# Sensors.net
KiCad netlist of a schematic drawn in EAGLE
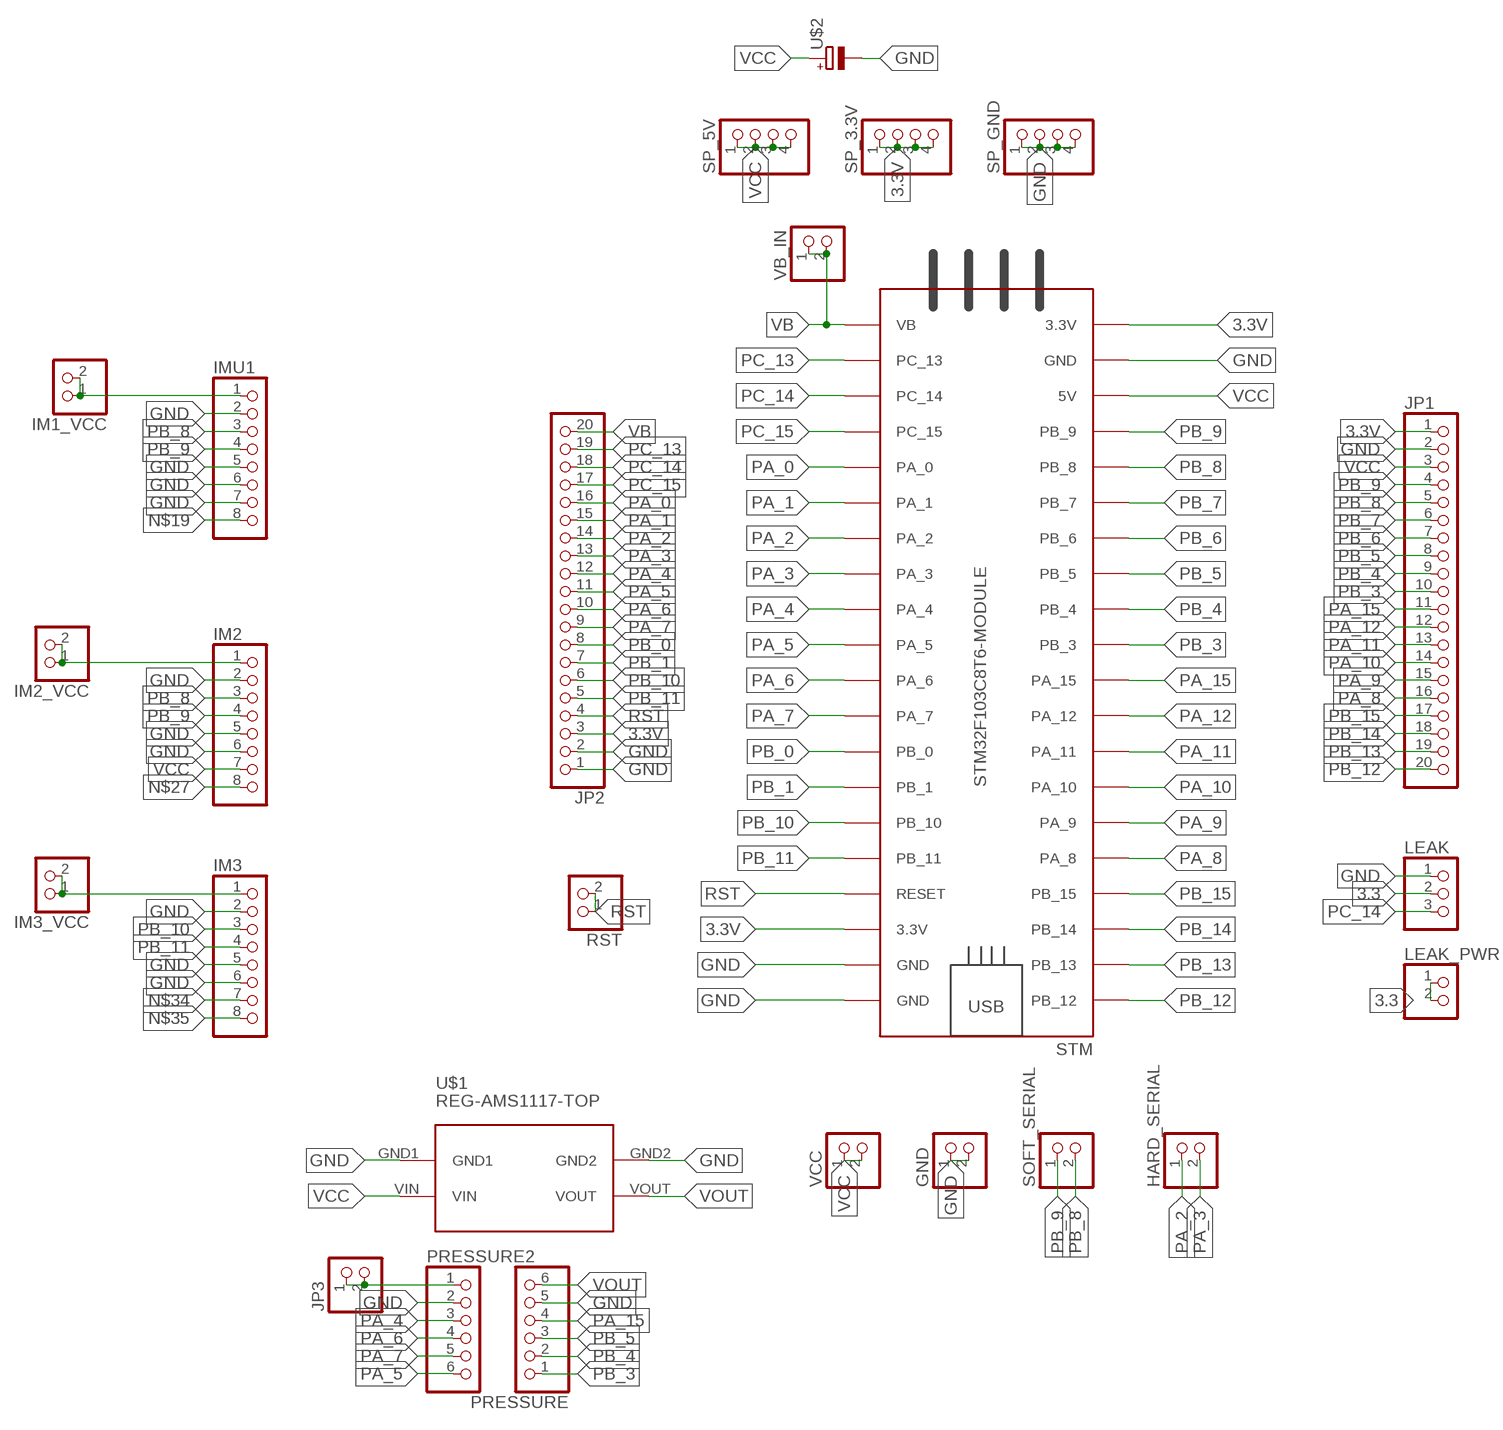
[diagram p0: schematic, sheet 1]

(export (version "E")
  (design (tool "Eeschema 10.0.6"))
  (components
    (comp (ref "GND")
      (value "PINHD-2_DATA")
      (footprint "eagle-import:1X02_DATA")
      (libsource (lib "eagle-import") (part "PINHD-2_DATA"))
    )
    (comp (ref "HARD_SERIAL")
      (value "PINHD-2_DATA")
      (footprint "eagle-import:1X02_DATA")
      (libsource (lib "eagle-import") (part "PINHD-2_DATA"))
    )
    (comp (ref "IM1_VCC")
      (value "PINHD-2_DATA")
      (footprint "eagle-import:1X02_DATA")
      (libsource (lib "eagle-import") (part "PINHD-2_DATA"))
    )
    (comp (ref "IM2")
      (value "PINHD-8_DATA")
      (footprint "eagle-import:1X08_DATA")
      (libsource (lib "eagle-import") (part "PINHD-8_DATA"))
    )
    (comp (ref "IM2_VCC")
      (value "PINHD-2_DATA")
      (footprint "eagle-import:1X02_DATA")
      (libsource (lib "eagle-import") (part "PINHD-2_DATA"))
    )
    (comp (ref "IM3")
      (value "PINHD-8_DATA")
      (footprint "eagle-import:1X08_DATA")
      (libsource (lib "eagle-import") (part "PINHD-8_DATA"))
    )
    (comp (ref "IM3_VCC")
      (value "PINHD-2_DATA")
      (footprint "eagle-import:1X02_DATA")
      (libsource (lib "eagle-import") (part "PINHD-2_DATA"))
    )
    (comp (ref "IMU1")
      (value "PINHD-8_DATA")
      (footprint "eagle-import:1X08_DATA")
      (libsource (lib "eagle-import") (part "PINHD-8_DATA"))
    )
    (comp (ref "JP1")
      (value "PINHD-1X20")
      (footprint "eagle-import:1X20")
      (libsource (lib "eagle-import") (part "PINHD-1X20"))
    )
    (comp (ref "JP2")
      (value "PINHD-1X20")
      (footprint "eagle-import:1X20")
      (libsource (lib "eagle-import") (part "PINHD-1X20"))
    )
    (comp (ref "JP3")
      (value "PINHD-2_DATA")
      (footprint "eagle-import:1X02_DATA")
      (libsource (lib "eagle-import") (part "PINHD-2_DATA"))
    )
    (comp (ref "LEAK")
      (value "PINHD-3_DATA")
      (footprint "eagle-import:1X03_DATA")
      (libsource (lib "eagle-import") (part "PINHD-3_DATA"))
    )
    (comp (ref "LEAK_PWR")
      (value "PINHD-2_DATA")
      (footprint "eagle-import:1X02_DATA")
      (libsource (lib "eagle-import") (part "PINHD-2_DATA"))
    )
    (comp (ref "PRESSURE")
      (value "PINHD-6_DATA")
      (footprint "eagle-import:1X06_DATA")
      (libsource (lib "eagle-import") (part "PINHD-6_DATA"))
    )
    (comp (ref "PRESSURE2")
      (value "PINHD-6_DATA")
      (footprint "eagle-import:1X06_DATA")
      (libsource (lib "eagle-import") (part "PINHD-6_DATA"))
    )
    (comp (ref "RST")
      (value "PINHD-2_DATA")
      (footprint "eagle-import:1X02_DATA")
      (libsource (lib "eagle-import") (part "PINHD-2_DATA"))
    )
    (comp (ref "SOFT_SERIAL")
      (value "PINHD-2_DATA")
      (footprint "eagle-import:1X02_DATA")
      (libsource (lib "eagle-import") (part "PINHD-2_DATA"))
    )
    (comp (ref "SP_3.3V")
      (value "PINHD-1X4")
      (footprint "eagle-import:1X04")
      (libsource (lib "eagle-import") (part "PINHD-1X4"))
    )
    (comp (ref "SP_5V")
      (value "PINHD-1X4")
      (footprint "eagle-import:1X04")
      (libsource (lib "eagle-import") (part "PINHD-1X4"))
    )
    (comp (ref "SP_GND")
      (value "PINHD-1X4")
      (footprint "eagle-import:1X04")
      (libsource (lib "eagle-import") (part "PINHD-1X4"))
    )
    (comp (ref "STM")
      (value "STM32F103C8T6-MODULE")
      (footprint "eagle-import:STM32F103C8T6-MODULE")
      (libsource (lib "eagle-import") (part "STM32F103C8T6-MODULE"))
    )
    (comp (ref "U$1")
      (value "REG-AMS1117-TOP")
      (footprint "eagle-import:REG-AMS1117_TOP")
      (libsource (lib "eagle-import") (part "REG-AMS1117-TOP"))
    )
    (comp (ref "U$2")
      (value "CAP_POL")
      (footprint "eagle-import:E3,5-8")
      (libsource (lib "eagle-import") (part "CAP_POL"))
    )
    (comp (ref "VB_IN")
      (value "PINHD-2_DATA")
      (footprint "eagle-import:1X02_DATA")
      (libsource (lib "eagle-import") (part "PINHD-2_DATA"))
    )
    (comp (ref "VCC")
      (value "PINHD-2_DATA")
      (footprint "eagle-import:1X02_DATA")
      (libsource (lib "eagle-import") (part "PINHD-2_DATA"))
    )
  )
  (nets
    (net (code "1") (name "3.3") (class "Default")
      (node (ref "LEAK") (pin "2") (pinfunction "2_2") (pintype "passive"))
      (node (ref "LEAK_PWR") (pin "1") (pinfunction "1_1") (pintype "passive"))
      (node (ref "LEAK_PWR") (pin "2") (pinfunction "2_2") (pintype "passive"))
    )
    (net (code "2") (name "3.3V") (class "Default")
      (node (ref "JP1") (pin "1") (pinfunction "1_1") (pintype "passive"))
      (node (ref "JP2") (pin "3") (pinfunction "3_3") (pintype "passive"))
      (node (ref "SP_3.3V") (pin "1") (pinfunction "1_1") (pintype "passive"))
      (node (ref "SP_3.3V") (pin "2") (pinfunction "2_2") (pintype "passive"))
      (node (ref "SP_3.3V") (pin "3") (pinfunction "3_3") (pintype "passive"))
      (node (ref "SP_3.3V") (pin "4") (pinfunction "4_4") (pintype "passive"))
      (node (ref "STM") (pin "3.3V_1") (pinfunction "3.3V_3.3V_1") (pintype "bidirectional"))
      (node (ref "STM") (pin "3.3V_2") (pinfunction "3.3V_3.3V_2") (pintype "bidirectional"))
    )
    (net (code "3") (name "GND") (class "Default")
      (node (ref "GND") (pin "1") (pinfunction "1_1") (pintype "passive"))
      (node (ref "GND") (pin "2") (pinfunction "2_2") (pintype "passive"))
      (node (ref "IM2") (pin "2") (pinfunction "2_2") (pintype "passive"))
      (node (ref "IM2") (pin "5") (pinfunction "5_5") (pintype "passive"))
      (node (ref "IM2") (pin "6") (pinfunction "6_6") (pintype "passive"))
      (node (ref "IM3") (pin "2") (pinfunction "2_2") (pintype "passive"))
      (node (ref "IM3") (pin "5") (pinfunction "5_5") (pintype "passive"))
      (node (ref "IM3") (pin "6") (pinfunction "6_6") (pintype "passive"))
      (node (ref "IMU1") (pin "2") (pinfunction "2_2") (pintype "passive"))
      (node (ref "IMU1") (pin "5") (pinfunction "5_5") (pintype "passive"))
      (node (ref "IMU1") (pin "6") (pinfunction "6_6") (pintype "passive"))
      (node (ref "IMU1") (pin "7") (pinfunction "7_7") (pintype "passive"))
      (node (ref "JP1") (pin "2") (pinfunction "2_2") (pintype "passive"))
      (node (ref "JP2") (pin "1") (pinfunction "1_1") (pintype "passive"))
      (node (ref "JP2") (pin "2") (pinfunction "2_2") (pintype "passive"))
      (node (ref "LEAK") (pin "1") (pinfunction "1_1") (pintype "passive"))
      (node (ref "PRESSURE") (pin "5") (pinfunction "5_5") (pintype "passive"))
      (node (ref "PRESSURE2") (pin "2") (pinfunction "2_2") (pintype "passive"))
      (node (ref "SP_GND") (pin "1") (pinfunction "1_1") (pintype "passive"))
      (node (ref "SP_GND") (pin "2") (pinfunction "2_2") (pintype "passive"))
      (node (ref "SP_GND") (pin "3") (pinfunction "3_3") (pintype "passive"))
      (node (ref "SP_GND") (pin "4") (pinfunction "4_4") (pintype "passive"))
      (node (ref "STM") (pin "GND_1") (pinfunction "GND_GND_1") (pintype "bidirectional"))
      (node (ref "STM") (pin "GND_2") (pinfunction "GND_GND_2") (pintype "bidirectional"))
      (node (ref "STM") (pin "GND_3") (pinfunction "GND_GND_3") (pintype "power_in"))
      (node (ref "U$1") (pin "GND1") (pinfunction "GND1_GND1") (pintype "bidirectional"))
      (node (ref "U$1") (pin "GND2") (pinfunction "GND2_GND2") (pintype "bidirectional"))
      (node (ref "U$2") (pin "-") (pinfunction "-_-") (pintype "passive"))
    )
    (net (code "4") (name "N$19") (class "Default")
      (node (ref "IMU1") (pin "8") (pinfunction "8_8") (pintype "passive"))
    )
    (net (code "5") (name "N$27") (class "Default")
      (node (ref "IM2") (pin "8") (pinfunction "8_8") (pintype "passive"))
    )
    (net (code "6") (name "N$34") (class "Default")
      (node (ref "IM3") (pin "7") (pinfunction "7_7") (pintype "passive"))
    )
    (net (code "7") (name "N$35") (class "Default")
      (node (ref "IM3") (pin "8") (pinfunction "8_8") (pintype "passive"))
    )
    (net (code "8") (name "Net-(IM1_VCC-Pad1)") (class "Default")
      (node (ref "IM1_VCC") (pin "1") (pinfunction "1_1") (pintype "passive"))
      (node (ref "IM1_VCC") (pin "2") (pinfunction "2_2") (pintype "passive"))
      (node (ref "IMU1") (pin "1") (pinfunction "1_1") (pintype "passive"))
    )
    (net (code "9") (name "Net-(IM2-Pad1)") (class "Default")
      (node (ref "IM2") (pin "1") (pinfunction "1_1") (pintype "passive"))
      (node (ref "IM2_VCC") (pin "1") (pinfunction "1_1") (pintype "passive"))
      (node (ref "IM2_VCC") (pin "2") (pinfunction "2_2") (pintype "passive"))
    )
    (net (code "10") (name "Net-(IM3-Pad1)") (class "Default")
      (node (ref "IM3") (pin "1") (pinfunction "1_1") (pintype "passive"))
      (node (ref "IM3_VCC") (pin "1") (pinfunction "1_1") (pintype "passive"))
      (node (ref "IM3_VCC") (pin "2") (pinfunction "2_2") (pintype "passive"))
    )
    (net (code "11") (name "Net-(JP3-Pad1)") (class "Default")
      (node (ref "JP3") (pin "1") (pinfunction "1_1") (pintype "passive"))
      (node (ref "JP3") (pin "2") (pinfunction "2_2") (pintype "passive"))
      (node (ref "PRESSURE2") (pin "1") (pinfunction "1_1") (pintype "passive"))
    )
    (net (code "12") (name "PA_0") (class "Default")
      (node (ref "JP2") (pin "16") (pinfunction "16_16") (pintype "passive"))
      (node (ref "STM") (pin "PA_0") (pinfunction "PA_0_PA_0") (pintype "bidirectional"))
    )
    (net (code "13") (name "PA_1") (class "Default")
      (node (ref "JP2") (pin "15") (pinfunction "15_15") (pintype "passive"))
      (node (ref "STM") (pin "PA_1") (pinfunction "PA_1_PA_1") (pintype "bidirectional"))
    )
    (net (code "14") (name "PA_2") (class "Default")
      (node (ref "HARD_SERIAL") (pin "1") (pinfunction "1_1") (pintype "passive"))
      (node (ref "JP2") (pin "14") (pinfunction "14_14") (pintype "passive"))
      (node (ref "STM") (pin "PA_2") (pinfunction "PA_2_PA_2") (pintype "bidirectional"))
    )
    (net (code "15") (name "PA_3") (class "Default")
      (node (ref "HARD_SERIAL") (pin "2") (pinfunction "2_2") (pintype "passive"))
      (node (ref "JP2") (pin "13") (pinfunction "13_13") (pintype "passive"))
      (node (ref "STM") (pin "PA_3") (pinfunction "PA_3_PA_3") (pintype "bidirectional"))
    )
    (net (code "16") (name "PA_4") (class "Default")
      (node (ref "JP2") (pin "12") (pinfunction "12_12") (pintype "passive"))
      (node (ref "PRESSURE2") (pin "3") (pinfunction "3_3") (pintype "passive"))
      (node (ref "STM") (pin "PA_4") (pinfunction "PA_4_PA_4") (pintype "bidirectional"))
    )
    (net (code "17") (name "PA_5") (class "Default")
      (node (ref "JP2") (pin "11") (pinfunction "11_11") (pintype "passive"))
      (node (ref "PRESSURE2") (pin "6") (pinfunction "6_6") (pintype "passive"))
      (node (ref "STM") (pin "PA_5") (pinfunction "PA_5_PA_5") (pintype "bidirectional"))
    )
    (net (code "18") (name "PA_6") (class "Default")
      (node (ref "JP2") (pin "10") (pinfunction "10_10") (pintype "passive"))
      (node (ref "PRESSURE2") (pin "4") (pinfunction "4_4") (pintype "passive"))
      (node (ref "STM") (pin "PA_6") (pinfunction "PA_6_PA_6") (pintype "bidirectional"))
    )
    (net (code "19") (name "PA_7") (class "Default")
      (node (ref "JP2") (pin "9") (pinfunction "9_9") (pintype "passive"))
      (node (ref "PRESSURE2") (pin "5") (pinfunction "5_5") (pintype "passive"))
      (node (ref "STM") (pin "PA_7") (pinfunction "PA_7_PA_7") (pintype "bidirectional"))
    )
    (net (code "20") (name "PA_8") (class "Default")
      (node (ref "JP1") (pin "16") (pinfunction "16_16") (pintype "passive"))
      (node (ref "STM") (pin "PA_8") (pinfunction "PA_8_PA_8") (pintype "bidirectional"))
    )
    (net (code "21") (name "PA_9") (class "Default")
      (node (ref "JP1") (pin "15") (pinfunction "15_15") (pintype "passive"))
      (node (ref "STM") (pin "PA_9") (pinfunction "PA_9_PA_9") (pintype "bidirectional"))
    )
    (net (code "22") (name "PA_10") (class "Default")
      (node (ref "JP1") (pin "14") (pinfunction "14_14") (pintype "passive"))
      (node (ref "STM") (pin "PA_10") (pinfunction "PA_10_PA_10") (pintype "bidirectional"))
    )
    (net (code "23") (name "PA_11") (class "Default")
      (node (ref "JP1") (pin "13") (pinfunction "13_13") (pintype "passive"))
      (node (ref "STM") (pin "PA_11") (pinfunction "PA_11_PA_11") (pintype "bidirectional"))
    )
    (net (code "24") (name "PA_12") (class "Default")
      (node (ref "JP1") (pin "12") (pinfunction "12_12") (pintype "passive"))
      (node (ref "STM") (pin "PA_12") (pinfunction "PA_12_PA_12") (pintype "bidirectional"))
    )
    (net (code "25") (name "PA_15") (class "Default")
      (node (ref "JP1") (pin "11") (pinfunction "11_11") (pintype "passive"))
      (node (ref "PRESSURE") (pin "4") (pinfunction "4_4") (pintype "passive"))
      (node (ref "STM") (pin "PA_15") (pinfunction "PA_15_PA_15") (pintype "bidirectional"))
    )
    (net (code "26") (name "PB_0") (class "Default")
      (node (ref "JP2") (pin "8") (pinfunction "8_8") (pintype "passive"))
      (node (ref "STM") (pin "PB_0") (pinfunction "PB_0_PB_0") (pintype "bidirectional"))
    )
    (net (code "27") (name "PB_1") (class "Default")
      (node (ref "JP2") (pin "7") (pinfunction "7_7") (pintype "passive"))
      (node (ref "STM") (pin "PB_1") (pinfunction "PB_1_PB_1") (pintype "bidirectional"))
    )
    (net (code "28") (name "PB_3") (class "Default")
      (node (ref "JP1") (pin "10") (pinfunction "10_10") (pintype "passive"))
      (node (ref "PRESSURE") (pin "1") (pinfunction "1_1") (pintype "passive"))
      (node (ref "STM") (pin "PB_3") (pinfunction "PB_3_PB_3") (pintype "bidirectional"))
    )
    (net (code "29") (name "PB_4") (class "Default")
      (node (ref "JP1") (pin "9") (pinfunction "9_9") (pintype "passive"))
      (node (ref "PRESSURE") (pin "2") (pinfunction "2_2") (pintype "passive"))
      (node (ref "STM") (pin "PB_4") (pinfunction "PB_4_PB_4") (pintype "bidirectional"))
    )
    (net (code "30") (name "PB_5") (class "Default")
      (node (ref "JP1") (pin "8") (pinfunction "8_8") (pintype "passive"))
      (node (ref "PRESSURE") (pin "3") (pinfunction "3_3") (pintype "passive"))
      (node (ref "STM") (pin "PB_5") (pinfunction "PB_5_PB_5") (pintype "bidirectional"))
    )
    (net (code "31") (name "PB_6") (class "Default")
      (node (ref "JP1") (pin "7") (pinfunction "7_7") (pintype "passive"))
      (node (ref "STM") (pin "PB_6") (pinfunction "PB_6_PB_6") (pintype "bidirectional"))
    )
    (net (code "32") (name "PB_7") (class "Default")
      (node (ref "JP1") (pin "6") (pinfunction "6_6") (pintype "passive"))
      (node (ref "STM") (pin "PB_7") (pinfunction "PB_7_PB_7") (pintype "bidirectional"))
    )
    (net (code "33") (name "PB_8") (class "Default")
      (node (ref "IM2") (pin "3") (pinfunction "3_3") (pintype "passive"))
      (node (ref "IMU1") (pin "3") (pinfunction "3_3") (pintype "passive"))
      (node (ref "JP1") (pin "5") (pinfunction "5_5") (pintype "passive"))
      (node (ref "SOFT_SERIAL") (pin "2") (pinfunction "2_2") (pintype "passive"))
      (node (ref "STM") (pin "PB_8") (pinfunction "PB_8_PB_8") (pintype "bidirectional"))
    )
    (net (code "34") (name "PB_9") (class "Default")
      (node (ref "IM2") (pin "4") (pinfunction "4_4") (pintype "passive"))
      (node (ref "IMU1") (pin "4") (pinfunction "4_4") (pintype "passive"))
      (node (ref "JP1") (pin "4") (pinfunction "4_4") (pintype "passive"))
      (node (ref "SOFT_SERIAL") (pin "1") (pinfunction "1_1") (pintype "passive"))
      (node (ref "STM") (pin "PB_9") (pinfunction "PB_9_PB_9") (pintype "bidirectional"))
    )
    (net (code "35") (name "PB_10") (class "Default")
      (node (ref "IM3") (pin "3") (pinfunction "3_3") (pintype "passive"))
      (node (ref "JP2") (pin "6") (pinfunction "6_6") (pintype "passive"))
      (node (ref "STM") (pin "PB_10") (pinfunction "PB_10_PB_10") (pintype "bidirectional"))
    )
    (net (code "36") (name "PB_11") (class "Default")
      (node (ref "IM3") (pin "4") (pinfunction "4_4") (pintype "passive"))
      (node (ref "JP2") (pin "5") (pinfunction "5_5") (pintype "passive"))
      (node (ref "STM") (pin "PB_11") (pinfunction "PB_11_PB_11") (pintype "bidirectional"))
    )
    (net (code "37") (name "PB_12") (class "Default")
      (node (ref "JP1") (pin "20") (pinfunction "20_20") (pintype "passive"))
      (node (ref "STM") (pin "PB_12") (pinfunction "PB_12_PB_12") (pintype "bidirectional"))
    )
    (net (code "38") (name "PB_13") (class "Default")
      (node (ref "JP1") (pin "19") (pinfunction "19_19") (pintype "passive"))
      (node (ref "STM") (pin "PB_13") (pinfunction "PB_13_PB_13") (pintype "bidirectional"))
    )
    (net (code "39") (name "PB_14") (class "Default")
      (node (ref "JP1") (pin "18") (pinfunction "18_18") (pintype "passive"))
      (node (ref "STM") (pin "PB_14") (pinfunction "PB_14_PB_14") (pintype "bidirectional"))
    )
    (net (code "40") (name "PB_15") (class "Default")
      (node (ref "JP1") (pin "17") (pinfunction "17_17") (pintype "passive"))
      (node (ref "STM") (pin "PB_15") (pinfunction "PB_15_PB_15") (pintype "bidirectional"))
    )
    (net (code "41") (name "PC_13") (class "Default")
      (node (ref "JP2") (pin "19") (pinfunction "19_19") (pintype "passive"))
      (node (ref "STM") (pin "PC_13") (pinfunction "PC_13_PC_13") (pintype "bidirectional"))
    )
    (net (code "42") (name "PC_14") (class "Default")
      (node (ref "JP2") (pin "18") (pinfunction "18_18") (pintype "passive"))
      (node (ref "LEAK") (pin "3") (pinfunction "3_3") (pintype "passive"))
      (node (ref "STM") (pin "PC_14") (pinfunction "PC_14_PC_14") (pintype "bidirectional"))
    )
    (net (code "43") (name "PC_15") (class "Default")
      (node (ref "JP2") (pin "17") (pinfunction "17_17") (pintype "passive"))
      (node (ref "STM") (pin "PC_15") (pinfunction "PC_15_PC_15") (pintype "bidirectional"))
    )
    (net (code "44") (name "RST") (class "Default")
      (node (ref "JP2") (pin "4") (pinfunction "4_4") (pintype "passive"))
      (node (ref "RST") (pin "1") (pinfunction "1_1") (pintype "passive"))
      (node (ref "RST") (pin "2") (pinfunction "2_2") (pintype "passive"))
      (node (ref "STM") (pin "RESET") (pinfunction "RESET_RESET") (pintype "bidirectional"))
    )
    (net (code "45") (name "VB") (class "Default")
      (node (ref "JP2") (pin "20") (pinfunction "20_20") (pintype "passive"))
      (node (ref "STM") (pin "VB") (pinfunction "VB_VB") (pintype "bidirectional"))
      (node (ref "VB_IN") (pin "1") (pinfunction "1_1") (pintype "passive"))
      (node (ref "VB_IN") (pin "2") (pinfunction "2_2") (pintype "passive"))
    )
    (net (code "46") (name "VCC") (class "Default")
      (node (ref "IM2") (pin "7") (pinfunction "7_7") (pintype "passive"))
      (node (ref "JP1") (pin "3") (pinfunction "3_3") (pintype "passive"))
      (node (ref "SP_5V") (pin "1") (pinfunction "1_1") (pintype "passive"))
      (node (ref "SP_5V") (pin "2") (pinfunction "2_2") (pintype "passive"))
      (node (ref "SP_5V") (pin "3") (pinfunction "3_3") (pintype "passive"))
      (node (ref "SP_5V") (pin "4") (pinfunction "4_4") (pintype "passive"))
      (node (ref "STM") (pin "5V") (pinfunction "5V_5V") (pintype "bidirectional"))
      (node (ref "U$1") (pin "VIN") (pinfunction "VIN_VIN") (pintype "bidirectional"))
      (node (ref "U$2") (pin "+") (pinfunction "+_+") (pintype "passive"))
      (node (ref "VCC") (pin "1") (pinfunction "1_1") (pintype "passive"))
      (node (ref "VCC") (pin "2") (pinfunction "2_2") (pintype "passive"))
    )
    (net (code "47") (name "VOUT") (class "Default")
      (node (ref "PRESSURE") (pin "6") (pinfunction "6_6") (pintype "passive"))
      (node (ref "U$1") (pin "VOUT") (pinfunction "VOUT_VOUT") (pintype "bidirectional"))
    )
  )
)
